# implant.net
KiCad netlist of a schematic drawn in EAGLE
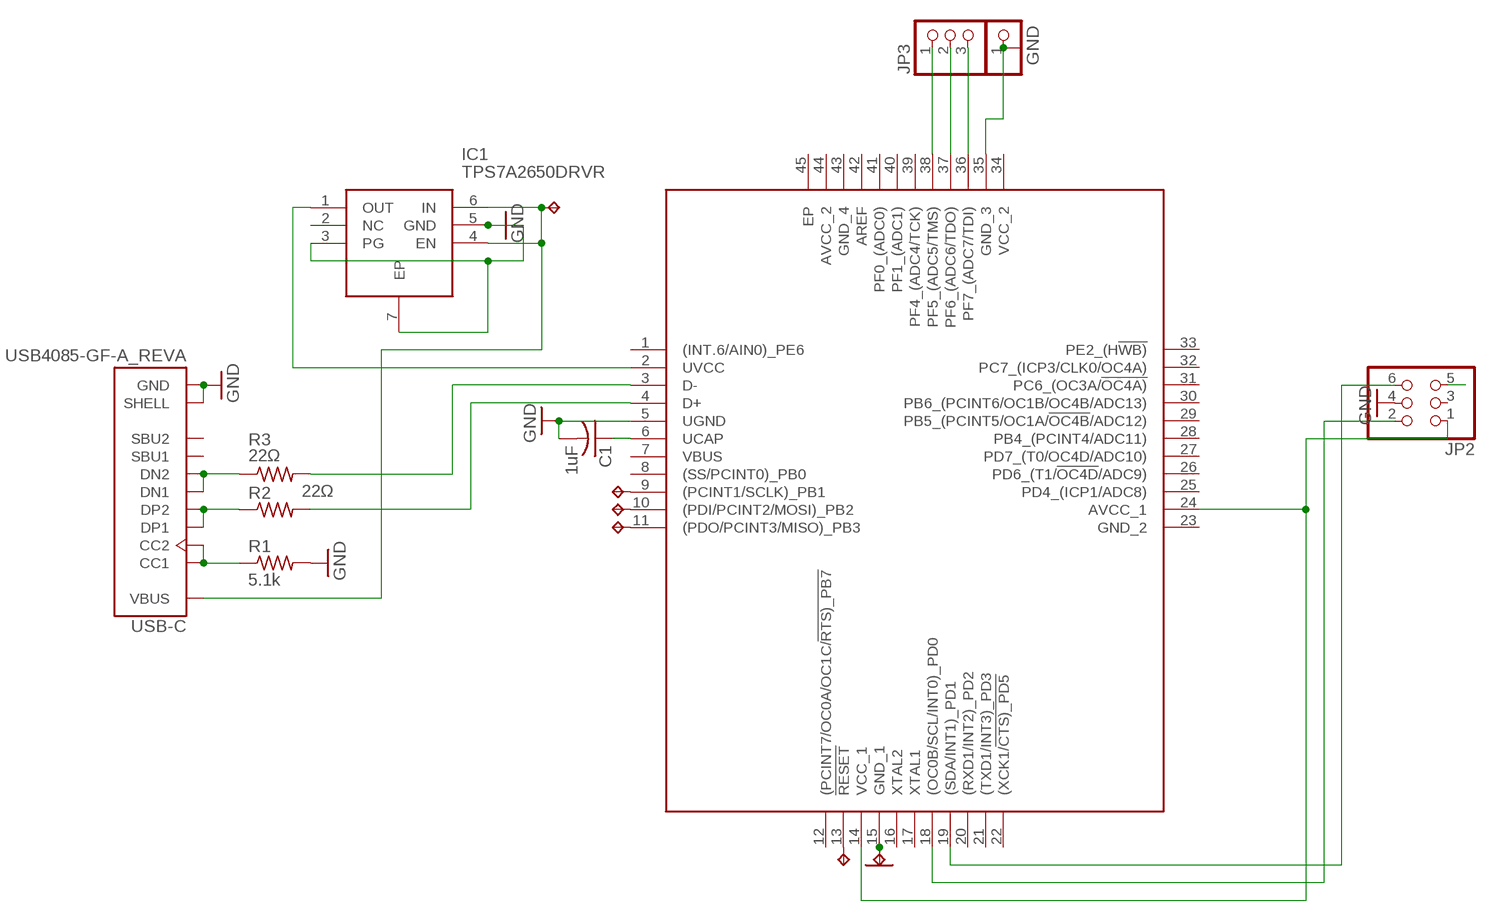
[diagram p0: schematic, sheet 1]

(export (version "E")
  (design (tool "Eeschema 10.0.6"))
  (components
    (comp (ref "5V")
      (value "TPTP17R")
      (footprint "eagle-import:TP17R")
      (libsource (lib "eagle-import") (part "TPTP17R"))
    )
    (comp (ref "C1")
      (value "1uF")
      (footprint "eagle-import:C0805")
      (libsource (lib "eagle-import") (part "C-USC0805"))
    )
    (comp (ref "GND")
      (value "TPTP17R")
      (footprint "eagle-import:TP17R")
      (libsource (lib "eagle-import") (part "TPTP17R"))
    )
    (comp (ref "IC1")
      (value "TPS7A2650DRVR")
      (footprint "eagle-import:SON65P200X200X80-7N")
      (fields (field (name "MOUSER_PART_NUMBER") "595-TPS7A2650DRVR"))
      (libsource (lib "eagle-import") (part "TPS7A2650DRVR"))
    )
    (comp (ref "IC2")
      (value "ATMEGA32U4-MU")
      (footprint "eagle-import:QFN50P700X700X100-45N")
      (fields (field (name "MOUSER_PART_NUMBER") "556-ATMEGA32U4-MU"))
      (libsource (lib "eagle-import") (part "ATMEGA32U4-MU"))
    )
    (comp (ref "JP1")
      (value "PINHD-1X1")
      (footprint "eagle-import:1X01")
      (libsource (lib "eagle-import") (part "PINHD-1X1"))
    )
    (comp (ref "JP2")
      (value "PINHD-2X3")
      (footprint "eagle-import:2X03")
      (libsource (lib "eagle-import") (part "PINHD-2X3"))
    )
    (comp (ref "JP3")
      (value "PINHD-1X3")
      (footprint "eagle-import:1X03")
      (libsource (lib "eagle-import") (part "PINHD-1X3"))
    )
    (comp (ref "MISO")
      (value "TPTP17R")
      (footprint "eagle-import:TP17R")
      (libsource (lib "eagle-import") (part "TPTP17R"))
    )
    (comp (ref "MOSI")
      (value "TPTP17R")
      (footprint "eagle-import:TP17R")
      (libsource (lib "eagle-import") (part "TPTP17R"))
    )
    (comp (ref "R1")
      (value "5.1k")
      (footprint "eagle-import:R0603")
      (libsource (lib "eagle-import") (part "R-US_R0603"))
    )
    (comp (ref "R2")
      (value "22Ω")
      (footprint "eagle-import:R0805")
      (libsource (lib "eagle-import") (part "R-US_R0805"))
    )
    (comp (ref "R3")
      (value "22Ω")
      (footprint "eagle-import:R0805")
      (libsource (lib "eagle-import") (part "R-US_R0805"))
    )
    (comp (ref "RST")
      (value "TPTP17R")
      (footprint "eagle-import:TP17R")
      (libsource (lib "eagle-import") (part "TPTP17R"))
    )
    (comp (ref "SCLK")
      (value "TPTP17R")
      (footprint "eagle-import:TP17R")
      (libsource (lib "eagle-import") (part "TPTP17R"))
    )
    (comp (ref "USB-C")
      (value "USB4085-GF-A_REVA")
      (footprint "eagle-import:GCT_USB4085-GF-A_REVA")
      (fields (field (name "MF") "Global Connector Technology") (field (name "MP") "USB4085-GF-A"))
      (libsource (lib "eagle-import") (part "USB4085-GF-A_REVA"))
    )
  )
  (nets
    (net (code "1") (name "GND") (class "Default")
      (node (ref "C1") (pin "2") (pinfunction "2_2") (pintype "passive"))
      (node (ref "GND") (pin "TP") (pinfunction "TP_TP") (pintype "input"))
      (node (ref "IC1") (pin "3") (pinfunction "PG_3") (pintype "bidirectional"))
      (node (ref "IC1") (pin "5") (pinfunction "GND_5") (pintype "bidirectional"))
      (node (ref "IC1") (pin "7") (pinfunction "EP_7") (pintype "bidirectional"))
      (node (ref "IC2") (pin "15") (pinfunction "GND_1_15") (pintype "bidirectional"))
      (node (ref "IC2") (pin "35") (pinfunction "GND_3_35") (pintype "bidirectional"))
      (node (ref "IC2") (pin "5") (pinfunction "UGND_5") (pintype "bidirectional"))
      (node (ref "JP1") (pin "1") (pinfunction "1_1") (pintype "passive"))
      (node (ref "JP2") (pin "4") (pinfunction "4_4") (pintype "passive"))
      (node (ref "R1") (pin "2") (pinfunction "2_2") (pintype "passive"))
      (node (ref "USB-C") (pin "A1") (pinfunction "GND_A1") (pintype "passive"))
      (node (ref "USB-C") (pin "A12") (pinfunction "GND_A12") (pintype "passive"))
      (node (ref "USB-C") (pin "B1") (pinfunction "GND_B1") (pintype "passive"))
      (node (ref "USB-C") (pin "B12") (pinfunction "GND_B12") (pintype "passive"))
      (node (ref "USB-C") (pin "P1") (pinfunction "SHELL_P1") (pintype "passive"))
      (node (ref "USB-C") (pin "P2") (pinfunction "SHELL_P2") (pintype "passive"))
      (node (ref "USB-C") (pin "P3") (pinfunction "SHELL_P3") (pintype "passive"))
      (node (ref "USB-C") (pin "P4") (pinfunction "SHELL_P4") (pintype "passive"))
    )
    (net (code "2") (name "Net-(IC1-EN)") (class "Default")
      (node (ref "5V") (pin "TP") (pinfunction "TP_TP") (pintype "input"))
      (node (ref "IC1") (pin "4") (pinfunction "EN_4") (pintype "bidirectional"))
      (node (ref "IC1") (pin "6") (pinfunction "IN_6") (pintype "bidirectional"))
      (node (ref "USB-C") (pin "A4") (pinfunction "VBUS_A4") (pintype "power_in"))
      (node (ref "USB-C") (pin "A9") (pinfunction "VBUS_A9") (pintype "power_in"))
      (node (ref "USB-C") (pin "B4") (pinfunction "VBUS_B4") (pintype "power_in"))
      (node (ref "USB-C") (pin "B9") (pinfunction "VBUS_B9") (pintype "power_in"))
    )
    (net (code "3") (name "Net-(IC1-OUT)") (class "Default")
      (node (ref "IC1") (pin "1") (pinfunction "OUT_1") (pintype "bidirectional"))
      (node (ref "IC2") (pin "2") (pinfunction "UVCC_2") (pintype "bidirectional"))
    )
    (net (code "4") (name "Net-(IC2-(OC0B{slash}SCL{slash}INT0)_PD0)") (class "Default")
      (node (ref "IC2") (pin "18") (pinfunction "(OC0B/SCL/INT0)_PD0_18") (pintype "bidirectional"))
      (node (ref "JP2") (pin "2") (pinfunction "2_2") (pintype "passive"))
    )
    (net (code "5") (name "Net-(IC2-(PCINT1{slash}SCLK)_PB1)") (class "Default")
      (node (ref "IC2") (pin "9") (pinfunction "(PCINT1/SCLK)_PB1_9") (pintype "bidirectional"))
      (node (ref "SCLK") (pin "TP") (pinfunction "TP_TP") (pintype "input"))
    )
    (net (code "6") (name "Net-(IC2-(PDI{slash}PCINT2{slash}MOSI)_PB2)") (class "Default")
      (node (ref "IC2") (pin "10") (pinfunction "(PDI/PCINT2/MOSI)_PB2_10") (pintype "bidirectional"))
      (node (ref "MOSI") (pin "TP") (pinfunction "TP_TP") (pintype "input"))
    )
    (net (code "7") (name "Net-(IC2-(PDO{slash}PCINT3{slash}MISO)_PB3)") (class "Default")
      (node (ref "IC2") (pin "11") (pinfunction "(PDO/PCINT3/MISO)_PB3_11") (pintype "bidirectional"))
      (node (ref "MISO") (pin "TP") (pinfunction "TP_TP") (pintype "input"))
    )
    (net (code "8") (name "Net-(IC2-(SDA{slash}INT1)_PD1)") (class "Default")
      (node (ref "IC2") (pin "19") (pinfunction "(SDA/INT1)_PD1_19") (pintype "bidirectional"))
      (node (ref "JP2") (pin "6") (pinfunction "6_6") (pintype "passive"))
    )
    (net (code "9") (name "Net-(IC2-AVCC_1)") (class "Default")
      (node (ref "IC2") (pin "14") (pinfunction "VCC_1_14") (pintype "bidirectional"))
      (node (ref "IC2") (pin "24") (pinfunction "AVCC_1_24") (pintype "bidirectional"))
      (node (ref "JP2") (pin "1") (pinfunction "1_1") (pintype "passive"))
    )
    (net (code "10") (name "Net-(IC2-D+)") (class "Default")
      (node (ref "IC2") (pin "4") (pinfunction "D+_4") (pintype "bidirectional"))
      (node (ref "R2") (pin "2") (pinfunction "2_2") (pintype "passive"))
    )
    (net (code "11") (name "Net-(IC2-D-)") (class "Default")
      (node (ref "IC2") (pin "3") (pinfunction "D-_3") (pintype "bidirectional"))
      (node (ref "R3") (pin "2") (pinfunction "2_2") (pintype "passive"))
    )
    (net (code "12") (name "Net-(IC2-PF5_(ADC5{slash}TMS))") (class "Default")
      (node (ref "IC2") (pin "38") (pinfunction "PF5_(ADC5/TMS)_38") (pintype "bidirectional"))
      (node (ref "JP3") (pin "1") (pinfunction "1_1") (pintype "passive"))
    )
    (net (code "13") (name "Net-(IC2-PF6_(ADC6{slash}TDO))") (class "Default")
      (node (ref "IC2") (pin "37") (pinfunction "PF6_(ADC6/TDO)_37") (pintype "bidirectional"))
      (node (ref "JP3") (pin "2") (pinfunction "2_2") (pintype "passive"))
    )
    (net (code "14") (name "Net-(IC2-PF7_(ADC7{slash}TDI))") (class "Default")
      (node (ref "IC2") (pin "36") (pinfunction "PF7_(ADC7/TDI)_36") (pintype "bidirectional"))
      (node (ref "JP3") (pin "3") (pinfunction "3_3") (pintype "passive"))
    )
    (net (code "15") (name "Net-(IC2-UCAP)") (class "Default")
      (node (ref "C1") (pin "1") (pinfunction "1_1") (pintype "passive"))
      (node (ref "IC2") (pin "6") (pinfunction "UCAP_6") (pintype "bidirectional"))
    )
    (net (code "16") (name "Net-(IC2-~{RESET})") (class "Default")
      (node (ref "IC2") (pin "13") (pinfunction "~{RESET}_13") (pintype "bidirectional"))
      (node (ref "RST") (pin "TP") (pinfunction "TP_TP") (pintype "input"))
    )
    (net (code "17") (name "Net-(USB-C-CC1)") (class "Default")
      (node (ref "R1") (pin "1") (pinfunction "1_1") (pintype "passive"))
      (node (ref "USB-C") (pin "A5") (pinfunction "CC1_A5") (pintype "bidirectional"))
      (node (ref "USB-C") (pin "B5") (pinfunction "CC2_B5") (pintype "bidirectional"))
    )
    (net (code "18") (name "Net-(USB-C-DN1)") (class "Default")
      (node (ref "R3") (pin "1") (pinfunction "1_1") (pintype "passive"))
      (node (ref "USB-C") (pin "A7") (pinfunction "DN1_A7") (pintype "bidirectional"))
      (node (ref "USB-C") (pin "B7") (pinfunction "DN2_B7") (pintype "bidirectional"))
    )
    (net (code "19") (name "Net-(USB-C-DP1)") (class "Default")
      (node (ref "R2") (pin "1") (pinfunction "1_1") (pintype "passive"))
      (node (ref "USB-C") (pin "A6") (pinfunction "DP1_A6") (pintype "bidirectional"))
      (node (ref "USB-C") (pin "B6") (pinfunction "DP2_B6") (pintype "bidirectional"))
    )
    (net (code "20") (name "unconnected-(IC1-NC-Pad2)") (class "Default")
      (node (ref "IC1") (pin "2") (pinfunction "NC_2") (pintype "no_connect"))
    )
    (net (code "21") (name "unconnected-(IC2-(INT.6{slash}AIN0)_PE6-Pad1)") (class "Default")
      (node (ref "IC2") (pin "1") (pinfunction "(INT.6/AIN0)_PE6_1") (pintype "bidirectional"))
    )
    (net (code "22") (name "unconnected-(IC2-(PCINT7{slash}OC0A{slash}OC1C{slash}~{RTS})_PB7-Pad12)") (class "Default")
      (node (ref "IC2") (pin "12") (pinfunction "(PCINT7/OC0A/OC1C/~{RTS})_PB7_12") (pintype "bidirectional"))
    )
    (net (code "23") (name "unconnected-(IC2-(RXD1{slash}INT2)_PD2-Pad20)") (class "Default")
      (node (ref "IC2") (pin "20") (pinfunction "(RXD1/INT2)_PD2_20") (pintype "bidirectional"))
    )
    (net (code "24") (name "unconnected-(IC2-(SS{slash}PCINT0)_PB0-Pad8)") (class "Default")
      (node (ref "IC2") (pin "8") (pinfunction "(SS/PCINT0)_PB0_8") (pintype "bidirectional"))
    )
    (net (code "25") (name "unconnected-(IC2-(TXD1{slash}INT3)_PD3-Pad21)") (class "Default")
      (node (ref "IC2") (pin "21") (pinfunction "(TXD1/INT3)_PD3_21") (pintype "bidirectional"))
    )
    (net (code "26") (name "unconnected-(IC2-(XCK1{slash}~{CTS})_PD5-Pad22)") (class "Default")
      (node (ref "IC2") (pin "22") (pinfunction "(XCK1/~{CTS})_PD5_22") (pintype "bidirectional"))
    )
    (net (code "27") (name "unconnected-(IC2-AREF-Pad42)") (class "Default")
      (node (ref "IC2") (pin "42") (pinfunction "AREF_42") (pintype "bidirectional"))
    )
    (net (code "28") (name "unconnected-(IC2-AVCC_2-Pad44)") (class "Default")
      (node (ref "IC2") (pin "44") (pinfunction "AVCC_2_44") (pintype "bidirectional"))
    )
    (net (code "29") (name "unconnected-(IC2-EP-Pad45)") (class "Default")
      (node (ref "IC2") (pin "45") (pinfunction "EP_45") (pintype "bidirectional"))
    )
    (net (code "30") (name "unconnected-(IC2-GND_2-Pad23)") (class "Default")
      (node (ref "IC2") (pin "23") (pinfunction "GND_2_23") (pintype "bidirectional"))
    )
    (net (code "31") (name "unconnected-(IC2-GND_4-Pad43)") (class "Default")
      (node (ref "IC2") (pin "43") (pinfunction "GND_4_43") (pintype "bidirectional"))
    )
    (net (code "32") (name "unconnected-(IC2-PB4_(PCINT4{slash}ADC11)-Pad28)") (class "Default")
      (node (ref "IC2") (pin "28") (pinfunction "PB4_(PCINT4/ADC11)_28") (pintype "bidirectional"))
    )
    (net (code "33") (name "unconnected-(IC2-PB5_(PCINT5{slash}OC1A{slash}~{OC4B}{slash}ADC12)-Pad29)") (class "Default")
      (node (ref "IC2") (pin "29") (pinfunction "PB5_(PCINT5/OC1A/~{OC4B}/ADC12)_29") (pintype "bidirectional"))
    )
    (net (code "34") (name "unconnected-(IC2-PB6_(PCINT6{slash}OC1B{slash}OC4B{slash}ADC13)-Pad30)") (class "Default")
      (node (ref "IC2") (pin "30") (pinfunction "PB6_(PCINT6/OC1B/OC4B/ADC13)_30") (pintype "bidirectional"))
    )
    (net (code "35") (name "unconnected-(IC2-PC6_(OC3A{slash}~{OC4A})-Pad31)") (class "Default")
      (node (ref "IC2") (pin "31") (pinfunction "PC6_(OC3A/~{OC4A})_31") (pintype "bidirectional"))
    )
    (net (code "36") (name "unconnected-(IC2-PC7_(ICP3{slash}CLK0{slash}OC4A)-Pad32)") (class "Default")
      (node (ref "IC2") (pin "32") (pinfunction "PC7_(ICP3/CLK0/OC4A)_32") (pintype "bidirectional"))
    )
    (net (code "37") (name "unconnected-(IC2-PD4_(ICP1{slash}ADC8)-Pad25)") (class "Default")
      (node (ref "IC2") (pin "25") (pinfunction "PD4_(ICP1/ADC8)_25") (pintype "bidirectional"))
    )
    (net (code "38") (name "unconnected-(IC2-PD6_(T1{slash}~{OC4D}{slash}ADC9)-Pad26)") (class "Default")
      (node (ref "IC2") (pin "26") (pinfunction "PD6_(T1/~{OC4D}/ADC9)_26") (pintype "bidirectional"))
    )
    (net (code "39") (name "unconnected-(IC2-PD7_(T0{slash}OC4D{slash}ADC10)-Pad27)") (class "Default")
      (node (ref "IC2") (pin "27") (pinfunction "PD7_(T0/OC4D/ADC10)_27") (pintype "bidirectional"))
    )
    (net (code "40") (name "unconnected-(IC2-PE2_(H~{WB})-Pad33)") (class "Default")
      (node (ref "IC2") (pin "33") (pinfunction "PE2_(H~{WB})_33") (pintype "bidirectional"))
    )
    (net (code "41") (name "unconnected-(IC2-PF0_(ADC0)-Pad41)") (class "Default")
      (node (ref "IC2") (pin "41") (pinfunction "PF0_(ADC0)_41") (pintype "bidirectional"))
    )
    (net (code "42") (name "unconnected-(IC2-PF1_(ADC1)-Pad40)") (class "Default")
      (node (ref "IC2") (pin "40") (pinfunction "PF1_(ADC1)_40") (pintype "bidirectional"))
    )
    (net (code "43") (name "unconnected-(IC2-PF4_(ADC4{slash}TCK)-Pad39)") (class "Default")
      (node (ref "IC2") (pin "39") (pinfunction "PF4_(ADC4/TCK)_39") (pintype "bidirectional"))
    )
    (net (code "44") (name "unconnected-(IC2-VBUS-Pad7)") (class "Default")
      (node (ref "IC2") (pin "7") (pinfunction "VBUS_7") (pintype "bidirectional"))
    )
    (net (code "45") (name "unconnected-(IC2-VCC_2-Pad34)") (class "Default")
      (node (ref "IC2") (pin "34") (pinfunction "VCC_2_34") (pintype "bidirectional"))
    )
    (net (code "46") (name "unconnected-(IC2-XTAL1-Pad17)") (class "Default")
      (node (ref "IC2") (pin "17") (pinfunction "XTAL1_17") (pintype "bidirectional"))
    )
    (net (code "47") (name "unconnected-(IC2-XTAL2-Pad16)") (class "Default")
      (node (ref "IC2") (pin "16") (pinfunction "XTAL2_16") (pintype "bidirectional"))
    )
    (net (code "48") (name "unconnected-(JP2-Pad3)") (class "Default")
      (node (ref "JP2") (pin "3") (pinfunction "3_3") (pintype "passive"))
    )
    (net (code "49") (name "unconnected-(JP2-Pad5)") (class "Default")
      (node (ref "JP2") (pin "5") (pinfunction "5_5") (pintype "passive"))
    )
    (net (code "50") (name "unconnected-(USB-C-SBU1-PadA8)") (class "Default")
      (node (ref "USB-C") (pin "A8") (pinfunction "SBU1_A8") (pintype "bidirectional"))
    )
    (net (code "51") (name "unconnected-(USB-C-SBU2-PadB8)") (class "Default")
      (node (ref "USB-C") (pin "B8") (pinfunction "SBU2_B8") (pintype "bidirectional"))
    )
  )
)
